# XMOS_MAX3420E.net
KiCad netlist of a schematic drawn in Altium Designer
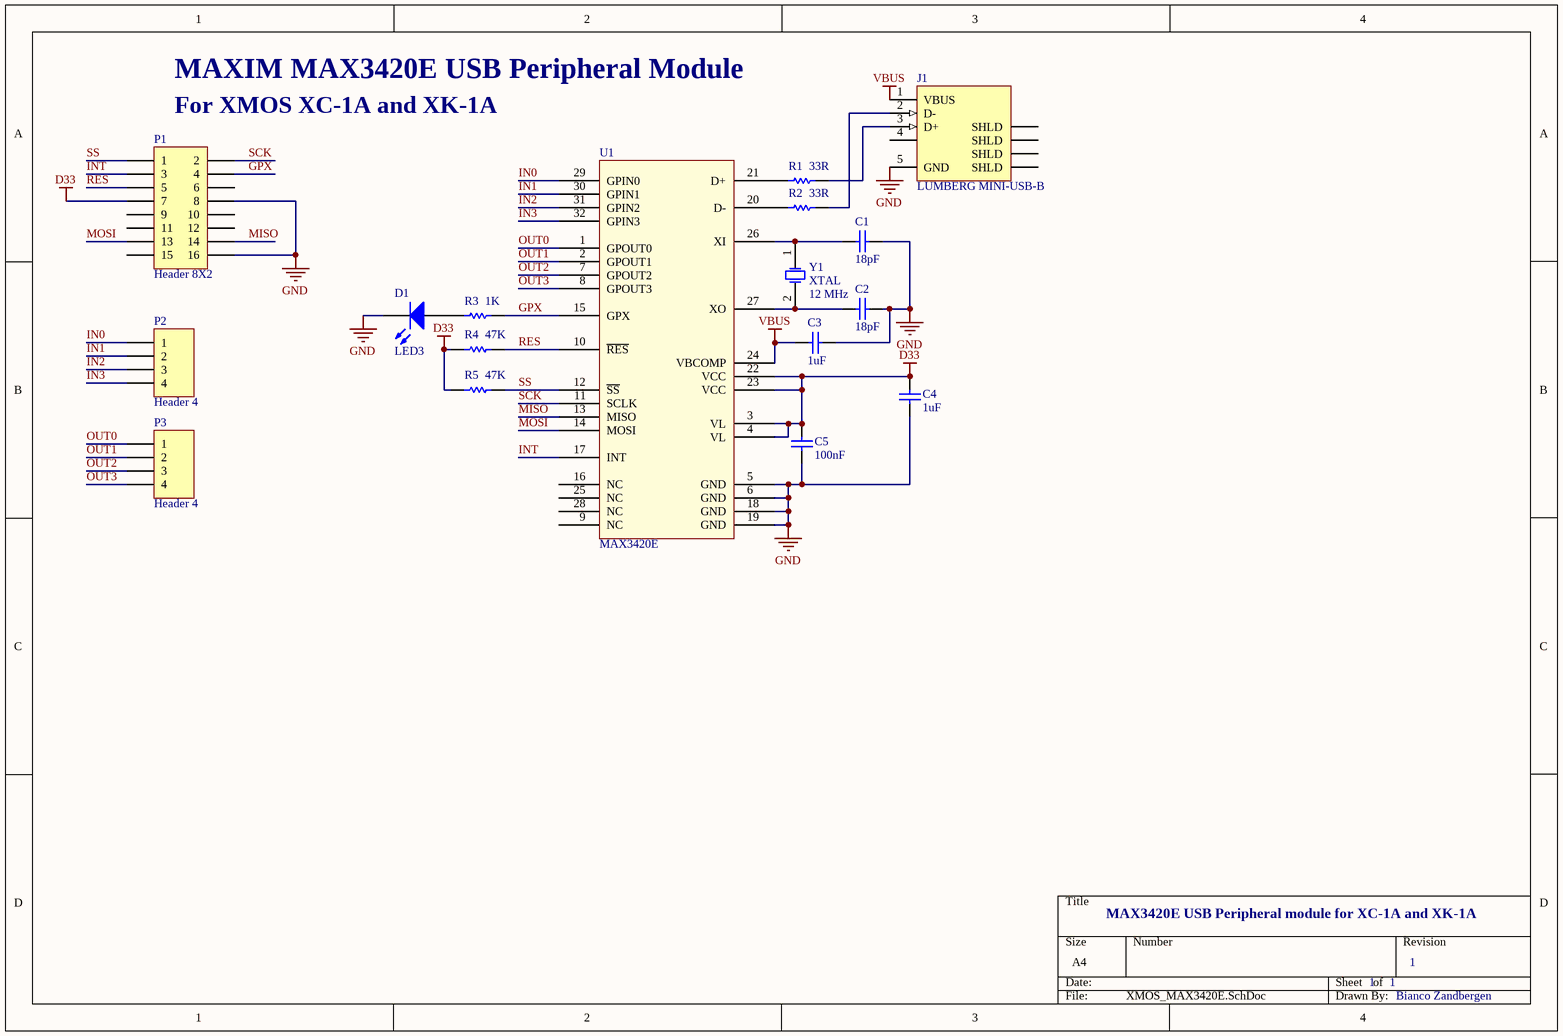
[diagram p0: XMOS_MAX3420E.SchDoc]

(export (version "E")
  (design (tool "Eeschema 10.0.6"))
  (components
    (comp (ref "C1")
      (value "18pF")
      (footprint "1608[0603]_CAP")
      (description "Capacitor")
      (fields
        (field (name "MANUFACTURER") "MURATA")
        (field (name "Comment") "Cap")
        (field (name "PUBLISHER") "Altium Limited")
      )
      (libsource (lib "xmos_common") (part "Cap"))
    )
    (comp (ref "C2")
      (value "18pF")
      (footprint "1608[0603]_CAP")
      (description "Capacitor")
      (fields (field (name "Comment") "Cap") (field (name "PUBLISHER") "Altium Limited"))
      (libsource (lib "xmos_common") (part "Cap"))
    )
    (comp (ref "C3")
      (value "1uF")
      (footprint "1608[0603]_CAP")
      (description "Capacitor")
      (fields
        (field (name "MANUFACTURER") "KEMET")
        (field (name "Comment") "Cap")
        (field (name "PUBLISHER") "Altium Limited")
      )
      (libsource (lib "xmos_common") (part "Cap"))
    )
    (comp (ref "C4")
      (value "1uF")
      (footprint "1608[0603]_CAP")
      (description "Capacitor")
      (fields (field (name "Comment") "Cap") (field (name "PUBLISHER") "Altium Limited"))
      (libsource (lib "xmos_common") (part "Cap"))
    )
    (comp (ref "C5")
      (value "100nF")
      (footprint "1608[0603]_CAP")
      (description "Capacitor")
      (fields
        (field (name "MANUFACTURER") "MURATA")
        (field (name "Comment") "Cap")
        (field (name "PUBLISHER") "Altium Limited")
      )
      (libsource (lib "xmos_common") (part "Cap"))
    )
    (comp (ref "D1")
      (value "LED3")
      (footprint "2012[0805]_LED")
      (description "SMD LED 0805")
      (fields (field (name "MANUFACTURER") "KINGBRIGHT") (field (name "PUBLISHER") "Altium Limited"))
      (libsource (lib "xmos_common") (part "LED3"))
    )
    (comp (ref "J1")
      (value "LUMBERG MINI-USB-B")
      (footprint "LUMBERG mini USB-B")
      (description "MINI USB TYPE B, RECEPTACLE, SMT")
      (fields (field (name "MANUFACTURER") "LUMBERG") (field (name "PUBLISHER") "Altium Limited"))
      (libsource (lib "xmos_common") (part "LUMBERG MINI-USB-B"))
    )
    (comp (ref "P1")
      (value "Header 8X2")
      (footprint "HDR2X8")
      (description "Header, 8-Pin, Dual row")
      (fields (field (name "MANUFACTURER") "FISCHER ELEKTRONIK") (field (name "PUBLISHER") "Altium Limited"))
      (libsource (lib "xmos_common") (part "Header 8X2"))
    )
    (comp (ref "P2")
      (value "Header 4")
      (footprint "HDR1X4")
      (description "Header, 4-Pin")
      (fields (field (name "PUBLISHER") "Altium Limited"))
      (libsource (lib "xmos_common") (part "Header 4"))
    )
    (comp (ref "P3")
      (value "Header 4")
      (footprint "HDR1X4")
      (description "Header, 4-Pin")
      (fields (field (name "PUBLISHER") "Altium Limited"))
      (libsource (lib "xmos_common") (part "Header 4"))
    )
    (comp (ref "R1")
      (value "33R")
      (footprint "1608[0603]_RES")
      (description "Resistor")
      (fields
        (field (name "MANUFACTURER") "PANASONIC")
        (field (name "Comment") "Res")
        (field (name "PUBLISHER") "Altium Limited")
      )
      (libsource (lib "xmos_common") (part "Res"))
    )
    (comp (ref "R2")
      (value "33R")
      (footprint "1608[0603]_RES")
      (description "Resistor")
      (fields (field (name "Comment") "Res") (field (name "PUBLISHER") "Altium Limited"))
      (libsource (lib "xmos_common") (part "Res"))
    )
    (comp (ref "R3")
      (value "1K")
      (footprint "1608[0603]_RES")
      (description "Resistor")
      (fields
        (field (name "MANUFACTURER") "PANASONIC")
        (field (name "Comment") "Res")
        (field (name "PUBLISHER") "Altium Limited")
      )
      (libsource (lib "xmos_common") (part "Res"))
    )
    (comp (ref "R4")
      (value "47K")
      (footprint "1608[0603]_RES")
      (description "Resistor")
      (fields (field (name "Comment") "Res") (field (name "PUBLISHER") "Altium Limited"))
      (libsource (lib "xmos_common") (part "Res"))
    )
    (comp (ref "R5")
      (value "47K")
      (footprint "1608[0603]_RES")
      (description "Resistor")
      (fields
        (field (name "MANUFACTURER") "PANASONIC")
        (field (name "Comment") "Res")
        (field (name "PUBLISHER") "Altium Limited")
      )
      (libsource (lib "xmos_common") (part "Res"))
    )
    (comp (ref "U1")
      (value "MAX3420E")
      (footprint "TQFP80P900X900-32N")
      (description "USB Controller SPI Interface")
      (fields (field (name "MANUFACTURER") "MAXIM IC"))
      (libsource (lib "xmos_common") (part "MAX3420E"))
    )
    (comp (ref "Y1")
      (value "XTAL")
      (footprint "HC49/4H_SMX")
      (description "Crystal Oscillator")
      (fields
        (field (name "ALTIUM_VALUE") "12 MHz")
        (field (name "MANUFACTURER") "ABRACON")
        (field (name "PUBLISHER") "Altium Limited")
      )
      (libsource (lib "xmos_common") (part "XTAL"))
    )
  )
  (nets
    (net (code "1") (name "/GPX") (class "Default")
      (node (ref "P1") (pin "4") (pinfunction "4_4") (pintype "passive"))
      (node (ref "R3") (pin "2") (pinfunction "2_2") (pintype "passive"))
      (node (ref "U1") (pin "15") (pinfunction "GPX_15") (pintype "passive"))
    )
    (net (code "2") (name "/IN0") (class "Default")
      (node (ref "P2") (pin "1") (pinfunction "1_1") (pintype "passive"))
      (node (ref "U1") (pin "29") (pinfunction "GPIN0_29") (pintype "passive"))
    )
    (net (code "3") (name "/IN1") (class "Default")
      (node (ref "P2") (pin "2") (pinfunction "2_2") (pintype "passive"))
      (node (ref "U1") (pin "30") (pinfunction "GPIN1_30") (pintype "passive"))
    )
    (net (code "4") (name "/IN2") (class "Default")
      (node (ref "P2") (pin "3") (pinfunction "3_3") (pintype "passive"))
      (node (ref "U1") (pin "31") (pinfunction "GPIN2_31") (pintype "passive"))
    )
    (net (code "5") (name "/IN3") (class "Default")
      (node (ref "P2") (pin "4") (pinfunction "4_4") (pintype "passive"))
      (node (ref "U1") (pin "32") (pinfunction "GPIN3_32") (pintype "passive"))
    )
    (net (code "6") (name "/INT") (class "Default")
      (node (ref "P1") (pin "3") (pinfunction "3_3") (pintype "passive"))
      (node (ref "U1") (pin "17") (pinfunction "INT_17") (pintype "passive"))
    )
    (net (code "7") (name "/MISO") (class "Default")
      (node (ref "P1") (pin "14") (pinfunction "14_14") (pintype "passive"))
      (node (ref "U1") (pin "13") (pinfunction "MISO_13") (pintype "passive"))
    )
    (net (code "8") (name "/MOSI") (class "Default")
      (node (ref "P1") (pin "13") (pinfunction "13_13") (pintype "passive"))
      (node (ref "U1") (pin "14") (pinfunction "MOSI_14") (pintype "passive"))
    )
    (net (code "9") (name "/OUT0") (class "Default")
      (node (ref "P3") (pin "1") (pinfunction "1_1") (pintype "passive"))
      (node (ref "U1") (pin "1") (pinfunction "GPOUT0_1") (pintype "passive"))
    )
    (net (code "10") (name "/OUT1") (class "Default")
      (node (ref "P3") (pin "2") (pinfunction "2_2") (pintype "passive"))
      (node (ref "U1") (pin "2") (pinfunction "GPOUT1_2") (pintype "passive"))
    )
    (net (code "11") (name "/OUT2") (class "Default")
      (node (ref "P3") (pin "3") (pinfunction "3_3") (pintype "passive"))
      (node (ref "U1") (pin "7") (pinfunction "GPOUT2_7") (pintype "passive"))
    )
    (net (code "12") (name "/OUT3") (class "Default")
      (node (ref "P3") (pin "4") (pinfunction "4_4") (pintype "passive"))
      (node (ref "U1") (pin "8") (pinfunction "GPOUT3_8") (pintype "passive"))
    )
    (net (code "13") (name "/RES") (class "Default")
      (node (ref "P1") (pin "5") (pinfunction "5_5") (pintype "passive"))
      (node (ref "R4") (pin "2") (pinfunction "2_2") (pintype "passive"))
      (node (ref "U1") (pin "10") (pinfunction "~{RES}_10") (pintype "passive"))
    )
    (net (code "14") (name "/SCK") (class "Default")
      (node (ref "P1") (pin "2") (pinfunction "2_2") (pintype "passive"))
      (node (ref "U1") (pin "11") (pinfunction "SCLK_11") (pintype "passive"))
    )
    (net (code "15") (name "/SS") (class "Default")
      (node (ref "P1") (pin "1") (pinfunction "1_1") (pintype "passive"))
      (node (ref "R5") (pin "2") (pinfunction "2_2") (pintype "passive"))
      (node (ref "U1") (pin "12") (pinfunction "~{SS}_12") (pintype "passive"))
    )
    (net (code "16") (name "D33") (class "Default")
      (node (ref "C4") (pin "2") (pinfunction "2_2") (pintype "passive"))
      (node (ref "C5") (pin "2") (pinfunction "2_2") (pintype "passive"))
      (node (ref "P1") (pin "7") (pinfunction "7_7") (pintype "passive"))
      (node (ref "R4") (pin "1") (pinfunction "1_1") (pintype "passive"))
      (node (ref "R5") (pin "1") (pinfunction "1_1") (pintype "passive"))
      (node (ref "U1") (pin "22") (pinfunction "VCC_22") (pintype "passive"))
      (node (ref "U1") (pin "23") (pinfunction "VCC_23") (pintype "passive"))
      (node (ref "U1") (pin "3") (pinfunction "VL_3") (pintype "passive"))
      (node (ref "U1") (pin "4") (pinfunction "VL_4") (pintype "passive"))
    )
    (net (code "17") (name "GND") (class "Default")
      (node (ref "C1") (pin "2") (pinfunction "2_2") (pintype "passive"))
      (node (ref "C2") (pin "2") (pinfunction "2_2") (pintype "passive"))
      (node (ref "C3") (pin "1") (pinfunction "1_1") (pintype "passive"))
      (node (ref "C4") (pin "1") (pinfunction "1_1") (pintype "passive"))
      (node (ref "C5") (pin "1") (pinfunction "1_1") (pintype "passive"))
      (node (ref "D1") (pin "2") (pinfunction "K_2") (pintype "passive"))
      (node (ref "J1") (pin "5") (pinfunction "GND_5") (pintype "passive"))
      (node (ref "P1") (pin "16") (pinfunction "16_16") (pintype "passive"))
      (node (ref "P1") (pin "8") (pinfunction "8_8") (pintype "passive"))
      (node (ref "U1") (pin "18") (pinfunction "GND_18") (pintype "passive"))
      (node (ref "U1") (pin "19") (pinfunction "GND_19") (pintype "passive"))
      (node (ref "U1") (pin "5") (pinfunction "GND_5") (pintype "passive"))
      (node (ref "U1") (pin "6") (pinfunction "GND_6") (pintype "passive"))
    )
    (net (code "18") (name "Net-(D1-A)") (class "Default")
      (node (ref "D1") (pin "1") (pinfunction "A_1") (pintype "passive"))
      (node (ref "R3") (pin "1") (pinfunction "1_1") (pintype "passive"))
    )
    (net (code "19") (name "Net-(J1-D+)") (class "Default")
      (node (ref "J1") (pin "3") (pinfunction "D+_3") (pintype "input"))
      (node (ref "R1") (pin "2") (pinfunction "2_2") (pintype "passive"))
    )
    (net (code "20") (name "Net-(J1-D-)") (class "Default")
      (node (ref "J1") (pin "2") (pinfunction "D-_2") (pintype "input"))
      (node (ref "R2") (pin "2") (pinfunction "2_2") (pintype "passive"))
    )
    (net (code "21") (name "Net-(U1-D+)") (class "Default")
      (node (ref "R1") (pin "1") (pinfunction "1_1") (pintype "passive"))
      (node (ref "U1") (pin "21") (pinfunction "D+_21") (pintype "passive"))
    )
    (net (code "22") (name "Net-(U1-D-)") (class "Default")
      (node (ref "R2") (pin "1") (pinfunction "1_1") (pintype "passive"))
      (node (ref "U1") (pin "20") (pinfunction "D-_20") (pintype "passive"))
    )
    (net (code "23") (name "Net-(U1-XI)") (class "Default")
      (node (ref "C1") (pin "1") (pinfunction "1_1") (pintype "passive"))
      (node (ref "U1") (pin "26") (pinfunction "XI_26") (pintype "passive"))
      (node (ref "Y1") (pin "1") (pinfunction "OSC1_1") (pintype "passive"))
    )
    (net (code "24") (name "Net-(U1-XO)") (class "Default")
      (node (ref "C2") (pin "1") (pinfunction "1_1") (pintype "passive"))
      (node (ref "U1") (pin "27") (pinfunction "XO_27") (pintype "passive"))
      (node (ref "Y1") (pin "2") (pinfunction "OSC2_2") (pintype "passive"))
    )
    (net (code "25") (name "VBUS") (class "Default")
      (node (ref "C3") (pin "2") (pinfunction "2_2") (pintype "passive"))
      (node (ref "J1") (pin "1") (pinfunction "VBUS_1") (pintype "power_in"))
      (node (ref "U1") (pin "24") (pinfunction "VBCOMP_24") (pintype "passive"))
    )
    (net (code "26") (name "unconnected-(J1-Pad4)") (class "Default")
      (node (ref "J1") (pin "4") (pintype "power_in"))
    )
    (net (code "27") (name "unconnected-(J1-SHLD-Pad6)") (class "Default")
      (node (ref "J1") (pin "6") (pinfunction "SHLD_6") (pintype "passive"))
    )
    (net (code "28") (name "unconnected-(J1-SHLD-Pad7)") (class "Default")
      (node (ref "J1") (pin "7") (pinfunction "SHLD_7") (pintype "passive"))
    )
    (net (code "29") (name "unconnected-(J1-SHLD-Pad8)") (class "Default")
      (node (ref "J1") (pin "8") (pinfunction "SHLD_8") (pintype "passive"))
    )
    (net (code "30") (name "unconnected-(J1-SHLD-Pad9)") (class "Default")
      (node (ref "J1") (pin "9") (pinfunction "SHLD_9") (pintype "passive"))
    )
    (net (code "31") (name "unconnected-(P1-Pad6)") (class "Default")
      (node (ref "P1") (pin "6") (pinfunction "6_6") (pintype "passive"))
    )
    (net (code "32") (name "unconnected-(P1-Pad9)") (class "Default")
      (node (ref "P1") (pin "9") (pinfunction "9_9") (pintype "passive"))
    )
    (net (code "33") (name "unconnected-(P1-Pad10)") (class "Default")
      (node (ref "P1") (pin "10") (pinfunction "10_10") (pintype "passive"))
    )
    (net (code "34") (name "unconnected-(P1-Pad11)") (class "Default")
      (node (ref "P1") (pin "11") (pinfunction "11_11") (pintype "passive"))
    )
    (net (code "35") (name "unconnected-(P1-Pad12)") (class "Default")
      (node (ref "P1") (pin "12") (pinfunction "12_12") (pintype "passive"))
    )
    (net (code "36") (name "unconnected-(P1-Pad15)") (class "Default")
      (node (ref "P1") (pin "15") (pinfunction "15_15") (pintype "passive"))
    )
    (net (code "37") (name "unconnected-(U1-NC-Pad9)") (class "Default")
      (node (ref "U1") (pin "9") (pinfunction "NC_9") (pintype "passive"))
    )
    (net (code "38") (name "unconnected-(U1-NC-Pad16)") (class "Default")
      (node (ref "U1") (pin "16") (pinfunction "NC_16") (pintype "passive"))
    )
    (net (code "39") (name "unconnected-(U1-NC-Pad25)") (class "Default")
      (node (ref "U1") (pin "25") (pinfunction "NC_25") (pintype "passive"))
    )
    (net (code "40") (name "unconnected-(U1-NC-Pad28)") (class "Default")
      (node (ref "U1") (pin "28") (pinfunction "NC_28") (pintype "passive"))
    )
  )
)
